# MUX2.net
KiCad netlist of a schematic drawn in EAGLE
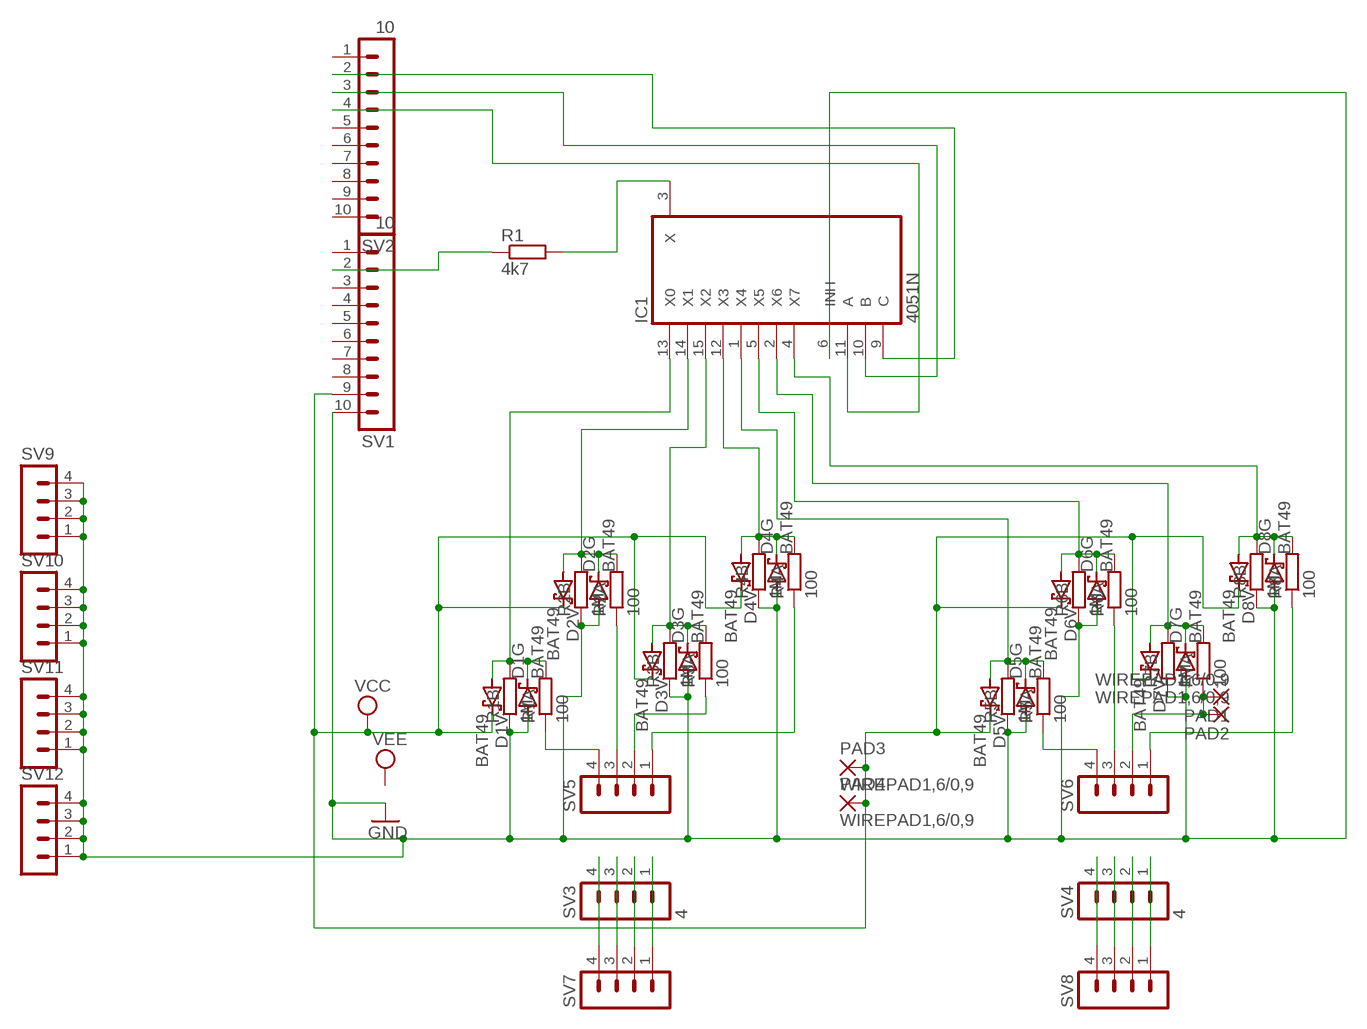
[diagram p0: schematic, sheet 1]

(export (version "E")
  (design (tool "Eeschema 10.0.6"))
  (components
    (comp (ref "D1G")
      (value "BAT49")
      (footprint "eagle-import:DO41-10")
      (libsource (lib "eagle-import") (part "BAT49"))
    )
    (comp (ref "D1V")
      (value "BAT49")
      (footprint "eagle-import:DO41-10")
      (libsource (lib "eagle-import") (part "BAT49"))
    )
    (comp (ref "D2G")
      (value "BAT49")
      (footprint "eagle-import:DO41-10")
      (libsource (lib "eagle-import") (part "BAT49"))
    )
    (comp (ref "D2V")
      (value "BAT49")
      (footprint "eagle-import:DO41-10")
      (libsource (lib "eagle-import") (part "BAT49"))
    )
    (comp (ref "D3G")
      (value "BAT49")
      (footprint "eagle-import:DO41-10")
      (libsource (lib "eagle-import") (part "BAT49"))
    )
    (comp (ref "D3V")
      (value "BAT49")
      (footprint "eagle-import:DO41-10")
      (libsource (lib "eagle-import") (part "BAT49"))
    )
    (comp (ref "D4G")
      (value "BAT49")
      (footprint "eagle-import:DO41-10")
      (libsource (lib "eagle-import") (part "BAT49"))
    )
    (comp (ref "D4V")
      (value "BAT49")
      (footprint "eagle-import:DO41-10")
      (libsource (lib "eagle-import") (part "BAT49"))
    )
    (comp (ref "D5G")
      (value "BAT49")
      (footprint "eagle-import:DO41-10")
      (libsource (lib "eagle-import") (part "BAT49"))
    )
    (comp (ref "D5V")
      (value "BAT49")
      (footprint "eagle-import:DO41-10")
      (libsource (lib "eagle-import") (part "BAT49"))
    )
    (comp (ref "D6G")
      (value "BAT49")
      (footprint "eagle-import:DO41-10")
      (libsource (lib "eagle-import") (part "BAT49"))
    )
    (comp (ref "D6V")
      (value "BAT49")
      (footprint "eagle-import:DO41-10")
      (libsource (lib "eagle-import") (part "BAT49"))
    )
    (comp (ref "D7G")
      (value "BAT49")
      (footprint "eagle-import:DO41-10")
      (libsource (lib "eagle-import") (part "BAT49"))
    )
    (comp (ref "D7V")
      (value "BAT49")
      (footprint "eagle-import:DO41-10")
      (libsource (lib "eagle-import") (part "BAT49"))
    )
    (comp (ref "D8G")
      (value "BAT49")
      (footprint "eagle-import:DO41-10")
      (libsource (lib "eagle-import") (part "BAT49"))
    )
    (comp (ref "D8V")
      (value "BAT49")
      (footprint "eagle-import:DO41-10")
      (libsource (lib "eagle-import") (part "BAT49"))
    )
    (comp (ref "IC1")
      (value "4051N")
      (footprint "eagle-import:DIL16")
      (libsource (lib "eagle-import") (part "4051N"))
    )
    (comp (ref "PAD1")
      (value "WIREPAD1,6/0,9")
      (footprint "eagle-import:1,6_0,9")
      (libsource (lib "eagle-import") (part "WIREPAD1,6/0,9"))
    )
    (comp (ref "PAD2")
      (value "WIREPAD1,6/0,9")
      (footprint "eagle-import:1,6_0,9")
      (libsource (lib "eagle-import") (part "WIREPAD1,6/0,9"))
    )
    (comp (ref "PAD3")
      (value "WIREPAD1,6/0,9")
      (footprint "eagle-import:1,6_0,9")
      (libsource (lib "eagle-import") (part "WIREPAD1,6/0,9"))
    )
    (comp (ref "PAD4")
      (value "WIREPAD1,6/0,9")
      (footprint "eagle-import:1,6_0,9")
      (libsource (lib "eagle-import") (part "WIREPAD1,6/0,9"))
    )
    (comp (ref "R1")
      (value "4k7")
      (footprint "eagle-import:0204_7")
      (libsource (lib "eagle-import") (part "R-EU_0204/7"))
    )
    (comp (ref "R1A")
      (value "100")
      (footprint "eagle-import:0204_7")
      (libsource (lib "eagle-import") (part "R-EU_0204/7"))
    )
    (comp (ref "R1B")
      (value "1M")
      (footprint "eagle-import:0204_7")
      (libsource (lib "eagle-import") (part "R-EU_0204/7"))
    )
    (comp (ref "R2A")
      (value "100")
      (footprint "eagle-import:0204_7")
      (libsource (lib "eagle-import") (part "R-EU_0204/7"))
    )
    (comp (ref "R2B")
      (value "1M")
      (footprint "eagle-import:0204_7")
      (libsource (lib "eagle-import") (part "R-EU_0204/7"))
    )
    (comp (ref "R3A")
      (value "100")
      (footprint "eagle-import:0204_7")
      (libsource (lib "eagle-import") (part "R-EU_0204/7"))
    )
    (comp (ref "R3B")
      (value "1M")
      (footprint "eagle-import:0204_7")
      (libsource (lib "eagle-import") (part "R-EU_0204/7"))
    )
    (comp (ref "R4A")
      (value "100")
      (footprint "eagle-import:0204_7")
      (libsource (lib "eagle-import") (part "R-EU_0204/7"))
    )
    (comp (ref "R4B")
      (value "1M")
      (footprint "eagle-import:0204_7")
      (libsource (lib "eagle-import") (part "R-EU_0204/7"))
    )
    (comp (ref "R5A")
      (value "100")
      (footprint "eagle-import:0204_7")
      (libsource (lib "eagle-import") (part "R-EU_0204/7"))
    )
    (comp (ref "R5B")
      (value "1M")
      (footprint "eagle-import:0204_7")
      (libsource (lib "eagle-import") (part "R-EU_0204/7"))
    )
    (comp (ref "R6A")
      (value "100")
      (footprint "eagle-import:0204_7")
      (libsource (lib "eagle-import") (part "R-EU_0204/7"))
    )
    (comp (ref "R6B")
      (value "1M")
      (footprint "eagle-import:0204_7")
      (libsource (lib "eagle-import") (part "R-EU_0204/7"))
    )
    (comp (ref "R7A")
      (value "100")
      (footprint "eagle-import:0204_7")
      (libsource (lib "eagle-import") (part "R-EU_0204/7"))
    )
    (comp (ref "R7B")
      (value "1M")
      (footprint "eagle-import:0204_7")
      (libsource (lib "eagle-import") (part "R-EU_0204/7"))
    )
    (comp (ref "R8A")
      (value "100")
      (footprint "eagle-import:0204_7")
      (libsource (lib "eagle-import") (part "R-EU_0204/7"))
    )
    (comp (ref "R8B")
      (value "1M")
      (footprint "eagle-import:0204_7")
      (libsource (lib "eagle-import") (part "R-EU_0204/7"))
    )
    (comp (ref "SV1")
      (value "10")
      (footprint "eagle-import:MA10-1")
      (libsource (lib "eagle-import") (part "MA10-1"))
    )
    (comp (ref "SV2")
      (value "10")
      (footprint "eagle-import:MA10-1")
      (libsource (lib "eagle-import") (part "MA10-1"))
    )
    (comp (ref "SV3")
      (value "4")
      (footprint "eagle-import:MA04-1")
      (libsource (lib "eagle-import") (part "MA04-1"))
    )
    (comp (ref "SV4")
      (value "4")
      (footprint "eagle-import:MA04-1")
      (libsource (lib "eagle-import") (part "MA04-1"))
    )
    (comp (ref "SV5")
      (value "MA04-1")
      (footprint "eagle-import:MA04-1")
      (libsource (lib "eagle-import") (part "MA04-1"))
    )
    (comp (ref "SV6")
      (value "MA04-1")
      (footprint "eagle-import:MA04-1")
      (libsource (lib "eagle-import") (part "MA04-1"))
    )
    (comp (ref "SV7")
      (value "MA04-1")
      (footprint "eagle-import:MA04-1")
      (libsource (lib "eagle-import") (part "MA04-1"))
    )
    (comp (ref "SV8")
      (value "MA04-1")
      (footprint "eagle-import:MA04-1")
      (libsource (lib "eagle-import") (part "MA04-1"))
    )
    (comp (ref "SV9")
      (value "MA04-1")
      (footprint "eagle-import:MA04-1")
      (libsource (lib "eagle-import") (part "MA04-1"))
    )
    (comp (ref "SV10")
      (value "MA04-1")
      (footprint "eagle-import:MA04-1")
      (libsource (lib "eagle-import") (part "MA04-1"))
    )
    (comp (ref "SV11")
      (value "MA04-1")
      (footprint "eagle-import:MA04-1")
      (libsource (lib "eagle-import") (part "MA04-1"))
    )
    (comp (ref "SV12")
      (value "MA04-1")
      (footprint "eagle-import:MA04-1")
      (libsource (lib "eagle-import") (part "MA04-1"))
    )
  )
  (nets
    (net (code "1") (name "GND") (class "Default")
      (node (ref "D1G") (pin "A") (pinfunction "A_A") (pintype "passive"))
      (node (ref "D2G") (pin "A") (pinfunction "A_A") (pintype "passive"))
      (node (ref "D3G") (pin "A") (pinfunction "A_A") (pintype "passive"))
      (node (ref "D4G") (pin "A") (pinfunction "A_A") (pintype "passive"))
      (node (ref "D5G") (pin "A") (pinfunction "A_A") (pintype "passive"))
      (node (ref "D6G") (pin "A") (pinfunction "A_A") (pintype "passive"))
      (node (ref "D7G") (pin "A") (pinfunction "A_A") (pintype "passive"))
      (node (ref "D8G") (pin "A") (pinfunction "A_A") (pintype "passive"))
      (node (ref "IC1") (pin "6") (pinfunction "INH_6") (pintype "input"))
      (node (ref "R1B") (pin "1") (pinfunction "1_1") (pintype "passive"))
      (node (ref "R2B") (pin "1") (pinfunction "1_1") (pintype "passive"))
      (node (ref "R3B") (pin "1") (pinfunction "1_1") (pintype "passive"))
      (node (ref "R4B") (pin "1") (pinfunction "1_1") (pintype "passive"))
      (node (ref "R5B") (pin "1") (pinfunction "1_1") (pintype "passive"))
      (node (ref "R6B") (pin "1") (pinfunction "1_1") (pintype "passive"))
      (node (ref "R7B") (pin "1") (pinfunction "1_1") (pintype "passive"))
      (node (ref "R8B") (pin "1") (pinfunction "1_1") (pintype "passive"))
      (node (ref "SV1") (pin "10") (pinfunction "10_10") (pintype "passive"))
      (node (ref "SV10") (pin "1") (pinfunction "1_1") (pintype "passive"))
      (node (ref "SV10") (pin "2") (pinfunction "2_2") (pintype "passive"))
      (node (ref "SV10") (pin "3") (pinfunction "3_3") (pintype "passive"))
      (node (ref "SV10") (pin "4") (pinfunction "4_4") (pintype "passive"))
      (node (ref "SV11") (pin "1") (pinfunction "1_1") (pintype "passive"))
      (node (ref "SV11") (pin "2") (pinfunction "2_2") (pintype "passive"))
      (node (ref "SV11") (pin "3") (pinfunction "3_3") (pintype "passive"))
      (node (ref "SV11") (pin "4") (pinfunction "4_4") (pintype "passive"))
      (node (ref "SV12") (pin "1") (pinfunction "1_1") (pintype "passive"))
      (node (ref "SV12") (pin "2") (pinfunction "2_2") (pintype "passive"))
      (node (ref "SV12") (pin "3") (pinfunction "3_3") (pintype "passive"))
      (node (ref "SV12") (pin "4") (pinfunction "4_4") (pintype "passive"))
      (node (ref "SV9") (pin "1") (pinfunction "1_1") (pintype "passive"))
      (node (ref "SV9") (pin "2") (pinfunction "2_2") (pintype "passive"))
      (node (ref "SV9") (pin "3") (pinfunction "3_3") (pintype "passive"))
      (node (ref "SV9") (pin "4") (pinfunction "4_4") (pintype "passive"))
    )
    (net (code "2") (name "Net-(IC1A-A)") (class "Default")
      (node (ref "IC1") (pin "11") (pinfunction "A_11") (pintype "input"))
      (node (ref "SV2") (pin "4") (pinfunction "4_4") (pintype "passive"))
    )
    (net (code "3") (name "Net-(IC1A-B)") (class "Default")
      (node (ref "IC1") (pin "10") (pinfunction "B_10") (pintype "input"))
      (node (ref "SV2") (pin "3") (pinfunction "3_3") (pintype "passive"))
    )
    (net (code "4") (name "Net-(IC1A-C)") (class "Default")
      (node (ref "IC1") (pin "9") (pinfunction "C_9") (pintype "input"))
      (node (ref "SV2") (pin "2") (pinfunction "2_2") (pintype "passive"))
    )
    (net (code "5") (name "Net-(IC1A-X)") (class "Default")
      (node (ref "IC1") (pin "3") (pinfunction "X_3") (pintype "bidirectional"))
      (node (ref "R1") (pin "2") (pinfunction "2_2") (pintype "passive"))
    )
    (net (code "6") (name "Net-(IC1A-X0)") (class "Default")
      (node (ref "D1G") (pin "C") (pinfunction "C_C") (pintype "passive"))
      (node (ref "D1V") (pin "A") (pinfunction "A_A") (pintype "passive"))
      (node (ref "IC1") (pin "13") (pinfunction "X0_13") (pintype "bidirectional"))
      (node (ref "R1A") (pin "2") (pinfunction "2_2") (pintype "passive"))
      (node (ref "R1B") (pin "2") (pinfunction "2_2") (pintype "passive"))
    )
    (net (code "7") (name "Net-(IC1A-X1)") (class "Default")
      (node (ref "D2G") (pin "C") (pinfunction "C_C") (pintype "passive"))
      (node (ref "D2V") (pin "A") (pinfunction "A_A") (pintype "passive"))
      (node (ref "IC1") (pin "14") (pinfunction "X1_14") (pintype "bidirectional"))
      (node (ref "R2A") (pin "2") (pinfunction "2_2") (pintype "passive"))
      (node (ref "R2B") (pin "2") (pinfunction "2_2") (pintype "passive"))
    )
    (net (code "8") (name "Net-(IC1A-X2)") (class "Default")
      (node (ref "D3G") (pin "C") (pinfunction "C_C") (pintype "passive"))
      (node (ref "D3V") (pin "A") (pinfunction "A_A") (pintype "passive"))
      (node (ref "IC1") (pin "15") (pinfunction "X2_15") (pintype "bidirectional"))
      (node (ref "R3A") (pin "2") (pinfunction "2_2") (pintype "passive"))
      (node (ref "R3B") (pin "2") (pinfunction "2_2") (pintype "passive"))
    )
    (net (code "9") (name "Net-(IC1A-X3)") (class "Default")
      (node (ref "D4G") (pin "C") (pinfunction "C_C") (pintype "passive"))
      (node (ref "D4V") (pin "A") (pinfunction "A_A") (pintype "passive"))
      (node (ref "IC1") (pin "12") (pinfunction "X3_12") (pintype "bidirectional"))
      (node (ref "R4A") (pin "2") (pinfunction "2_2") (pintype "passive"))
      (node (ref "R4B") (pin "2") (pinfunction "2_2") (pintype "passive"))
    )
    (net (code "10") (name "Net-(IC1A-X4)") (class "Default")
      (node (ref "D5G") (pin "C") (pinfunction "C_C") (pintype "passive"))
      (node (ref "D5V") (pin "A") (pinfunction "A_A") (pintype "passive"))
      (node (ref "IC1") (pin "1") (pinfunction "X4_1") (pintype "bidirectional"))
      (node (ref "R5A") (pin "2") (pinfunction "2_2") (pintype "passive"))
      (node (ref "R5B") (pin "2") (pinfunction "2_2") (pintype "passive"))
    )
    (net (code "11") (name "Net-(IC1A-X5)") (class "Default")
      (node (ref "D6G") (pin "C") (pinfunction "C_C") (pintype "passive"))
      (node (ref "D6V") (pin "A") (pinfunction "A_A") (pintype "passive"))
      (node (ref "IC1") (pin "5") (pinfunction "X5_5") (pintype "bidirectional"))
      (node (ref "R6A") (pin "2") (pinfunction "2_2") (pintype "passive"))
      (node (ref "R6B") (pin "2") (pinfunction "2_2") (pintype "passive"))
    )
    (net (code "12") (name "Net-(IC1A-X6)") (class "Default")
      (node (ref "D7G") (pin "C") (pinfunction "C_C") (pintype "passive"))
      (node (ref "D7V") (pin "A") (pinfunction "A_A") (pintype "passive"))
      (node (ref "IC1") (pin "2") (pinfunction "X6_2") (pintype "bidirectional"))
      (node (ref "R7A") (pin "2") (pinfunction "2_2") (pintype "passive"))
      (node (ref "R7B") (pin "2") (pinfunction "2_2") (pintype "passive"))
    )
    (net (code "13") (name "Net-(IC1A-X7)") (class "Default")
      (node (ref "D8G") (pin "C") (pinfunction "C_C") (pintype "passive"))
      (node (ref "D8V") (pin "A") (pinfunction "A_A") (pintype "passive"))
      (node (ref "IC1") (pin "4") (pinfunction "X7_4") (pintype "bidirectional"))
      (node (ref "R8A") (pin "2") (pinfunction "2_2") (pintype "passive"))
      (node (ref "R8B") (pin "2") (pinfunction "2_2") (pintype "passive"))
    )
    (net (code "14") (name "Net-(PAD1-P)") (class "Default")
      (node (ref "PAD1") (pin "1") (pinfunction "P_1") (pintype "passive"))
      (node (ref "PAD2") (pin "1") (pinfunction "P_1") (pintype "passive"))
      (node (ref "R7A") (pin "1") (pinfunction "1_1") (pintype "passive"))
      (node (ref "SV6") (pin "2") (pinfunction "2_2") (pintype "passive"))
    )
    (net (code "15") (name "Net-(R1-Pad1)") (class "Default")
      (node (ref "R1") (pin "1") (pinfunction "1_1") (pintype "passive"))
      (node (ref "SV1") (pin "2") (pinfunction "2_2") (pintype "passive"))
    )
    (net (code "16") (name "Net-(R1A-Pad1)") (class "Default")
      (node (ref "R1A") (pin "1") (pinfunction "1_1") (pintype "passive"))
      (node (ref "SV5") (pin "4") (pinfunction "4_4") (pintype "passive"))
    )
    (net (code "17") (name "Net-(R2A-Pad1)") (class "Default")
      (node (ref "R2A") (pin "1") (pinfunction "1_1") (pintype "passive"))
      (node (ref "SV5") (pin "3") (pinfunction "3_3") (pintype "passive"))
    )
    (net (code "18") (name "Net-(R3A-Pad1)") (class "Default")
      (node (ref "R3A") (pin "1") (pinfunction "1_1") (pintype "passive"))
      (node (ref "SV5") (pin "2") (pinfunction "2_2") (pintype "passive"))
    )
    (net (code "19") (name "Net-(R4A-Pad1)") (class "Default")
      (node (ref "R4A") (pin "1") (pinfunction "1_1") (pintype "passive"))
      (node (ref "SV5") (pin "1") (pinfunction "1_1") (pintype "passive"))
    )
    (net (code "20") (name "Net-(R5A-Pad1)") (class "Default")
      (node (ref "R5A") (pin "1") (pinfunction "1_1") (pintype "passive"))
      (node (ref "SV6") (pin "4") (pinfunction "4_4") (pintype "passive"))
    )
    (net (code "21") (name "Net-(R6A-Pad1)") (class "Default")
      (node (ref "R6A") (pin "1") (pinfunction "1_1") (pintype "passive"))
      (node (ref "SV6") (pin "3") (pinfunction "3_3") (pintype "passive"))
    )
    (net (code "22") (name "Net-(R8A-Pad1)") (class "Default")
      (node (ref "R8A") (pin "1") (pinfunction "1_1") (pintype "passive"))
      (node (ref "SV6") (pin "1") (pinfunction "1_1") (pintype "passive"))
    )
    (net (code "23") (name "Net-(SV3-Pad1)") (class "Default")
      (node (ref "SV3") (pin "1") (pinfunction "1_1") (pintype "passive"))
      (node (ref "SV7") (pin "1") (pinfunction "1_1") (pintype "passive"))
    )
    (net (code "24") (name "Net-(SV3-Pad2)") (class "Default")
      (node (ref "SV3") (pin "2") (pinfunction "2_2") (pintype "passive"))
      (node (ref "SV7") (pin "2") (pinfunction "2_2") (pintype "passive"))
    )
    (net (code "25") (name "Net-(SV3-Pad3)") (class "Default")
      (node (ref "SV3") (pin "3") (pinfunction "3_3") (pintype "passive"))
      (node (ref "SV7") (pin "3") (pinfunction "3_3") (pintype "passive"))
    )
    (net (code "26") (name "Net-(SV3-Pad4)") (class "Default")
      (node (ref "SV3") (pin "4") (pinfunction "4_4") (pintype "passive"))
      (node (ref "SV7") (pin "4") (pinfunction "4_4") (pintype "passive"))
    )
    (net (code "27") (name "Net-(SV4-Pad1)") (class "Default")
      (node (ref "SV4") (pin "1") (pinfunction "1_1") (pintype "passive"))
      (node (ref "SV8") (pin "1") (pinfunction "1_1") (pintype "passive"))
    )
    (net (code "28") (name "Net-(SV4-Pad2)") (class "Default")
      (node (ref "SV4") (pin "2") (pinfunction "2_2") (pintype "passive"))
      (node (ref "SV8") (pin "2") (pinfunction "2_2") (pintype "passive"))
    )
    (net (code "29") (name "Net-(SV4-Pad3)") (class "Default")
      (node (ref "SV4") (pin "3") (pinfunction "3_3") (pintype "passive"))
      (node (ref "SV8") (pin "3") (pinfunction "3_3") (pintype "passive"))
    )
    (net (code "30") (name "Net-(SV4-Pad4)") (class "Default")
      (node (ref "SV4") (pin "4") (pinfunction "4_4") (pintype "passive"))
      (node (ref "SV8") (pin "4") (pinfunction "4_4") (pintype "passive"))
    )
    (net (code "31") (name "VCC") (class "Default")
      (node (ref "D1V") (pin "C") (pinfunction "C_C") (pintype "passive"))
      (node (ref "D2V") (pin "C") (pinfunction "C_C") (pintype "passive"))
      (node (ref "D3V") (pin "C") (pinfunction "C_C") (pintype "passive"))
      (node (ref "D4V") (pin "C") (pinfunction "C_C") (pintype "passive"))
      (node (ref "D5V") (pin "C") (pinfunction "C_C") (pintype "passive"))
      (node (ref "D6V") (pin "C") (pinfunction "C_C") (pintype "passive"))
      (node (ref "D7V") (pin "C") (pinfunction "C_C") (pintype "passive"))
      (node (ref "D8V") (pin "C") (pinfunction "C_C") (pintype "passive"))
      (node (ref "PAD3") (pin "1") (pinfunction "P_1") (pintype "passive"))
      (node (ref "PAD4") (pin "1") (pinfunction "P_1") (pintype "passive"))
      (node (ref "SV1") (pin "9") (pinfunction "9_9") (pintype "passive"))
    )
    (net (code "33") (name "unconnected-(SV1-Pad1)") (class "Default")
      (node (ref "SV1") (pin "1") (pinfunction "1_1") (pintype "passive"))
    )
    (net (code "34") (name "unconnected-(SV1-Pad3)") (class "Default")
      (node (ref "SV1") (pin "3") (pinfunction "3_3") (pintype "passive"))
    )
    (net (code "35") (name "unconnected-(SV1-Pad4)") (class "Default")
      (node (ref "SV1") (pin "4") (pinfunction "4_4") (pintype "passive"))
    )
    (net (code "36") (name "unconnected-(SV1-Pad5)") (class "Default")
      (node (ref "SV1") (pin "5") (pinfunction "5_5") (pintype "passive"))
    )
    (net (code "37") (name "unconnected-(SV1-Pad6)") (class "Default")
      (node (ref "SV1") (pin "6") (pinfunction "6_6") (pintype "passive"))
    )
    (net (code "38") (name "unconnected-(SV1-Pad7)") (class "Default")
      (node (ref "SV1") (pin "7") (pinfunction "7_7") (pintype "passive"))
    )
    (net (code "39") (name "unconnected-(SV1-Pad8)") (class "Default")
      (node (ref "SV1") (pin "8") (pinfunction "8_8") (pintype "passive"))
    )
    (net (code "40") (name "unconnected-(SV2-Pad1)") (class "Default")
      (node (ref "SV2") (pin "1") (pinfunction "1_1") (pintype "passive"))
    )
    (net (code "41") (name "unconnected-(SV2-Pad5)") (class "Default")
      (node (ref "SV2") (pin "5") (pinfunction "5_5") (pintype "passive"))
    )
    (net (code "42") (name "unconnected-(SV2-Pad6)") (class "Default")
      (node (ref "SV2") (pin "6") (pinfunction "6_6") (pintype "passive"))
    )
    (net (code "43") (name "unconnected-(SV2-Pad7)") (class "Default")
      (node (ref "SV2") (pin "7") (pinfunction "7_7") (pintype "passive"))
    )
    (net (code "44") (name "unconnected-(SV2-Pad8)") (class "Default")
      (node (ref "SV2") (pin "8") (pinfunction "8_8") (pintype "passive"))
    )
    (net (code "45") (name "unconnected-(SV2-Pad9)") (class "Default")
      (node (ref "SV2") (pin "9") (pinfunction "9_9") (pintype "passive"))
    )
    (net (code "46") (name "unconnected-(SV2-Pad10)") (class "Default")
      (node (ref "SV2") (pin "10") (pinfunction "10_10") (pintype "passive"))
    )
  )
)
